# display_zm1000_rev_a.net
KiCad netlist of a schematic drawn in EAGLE
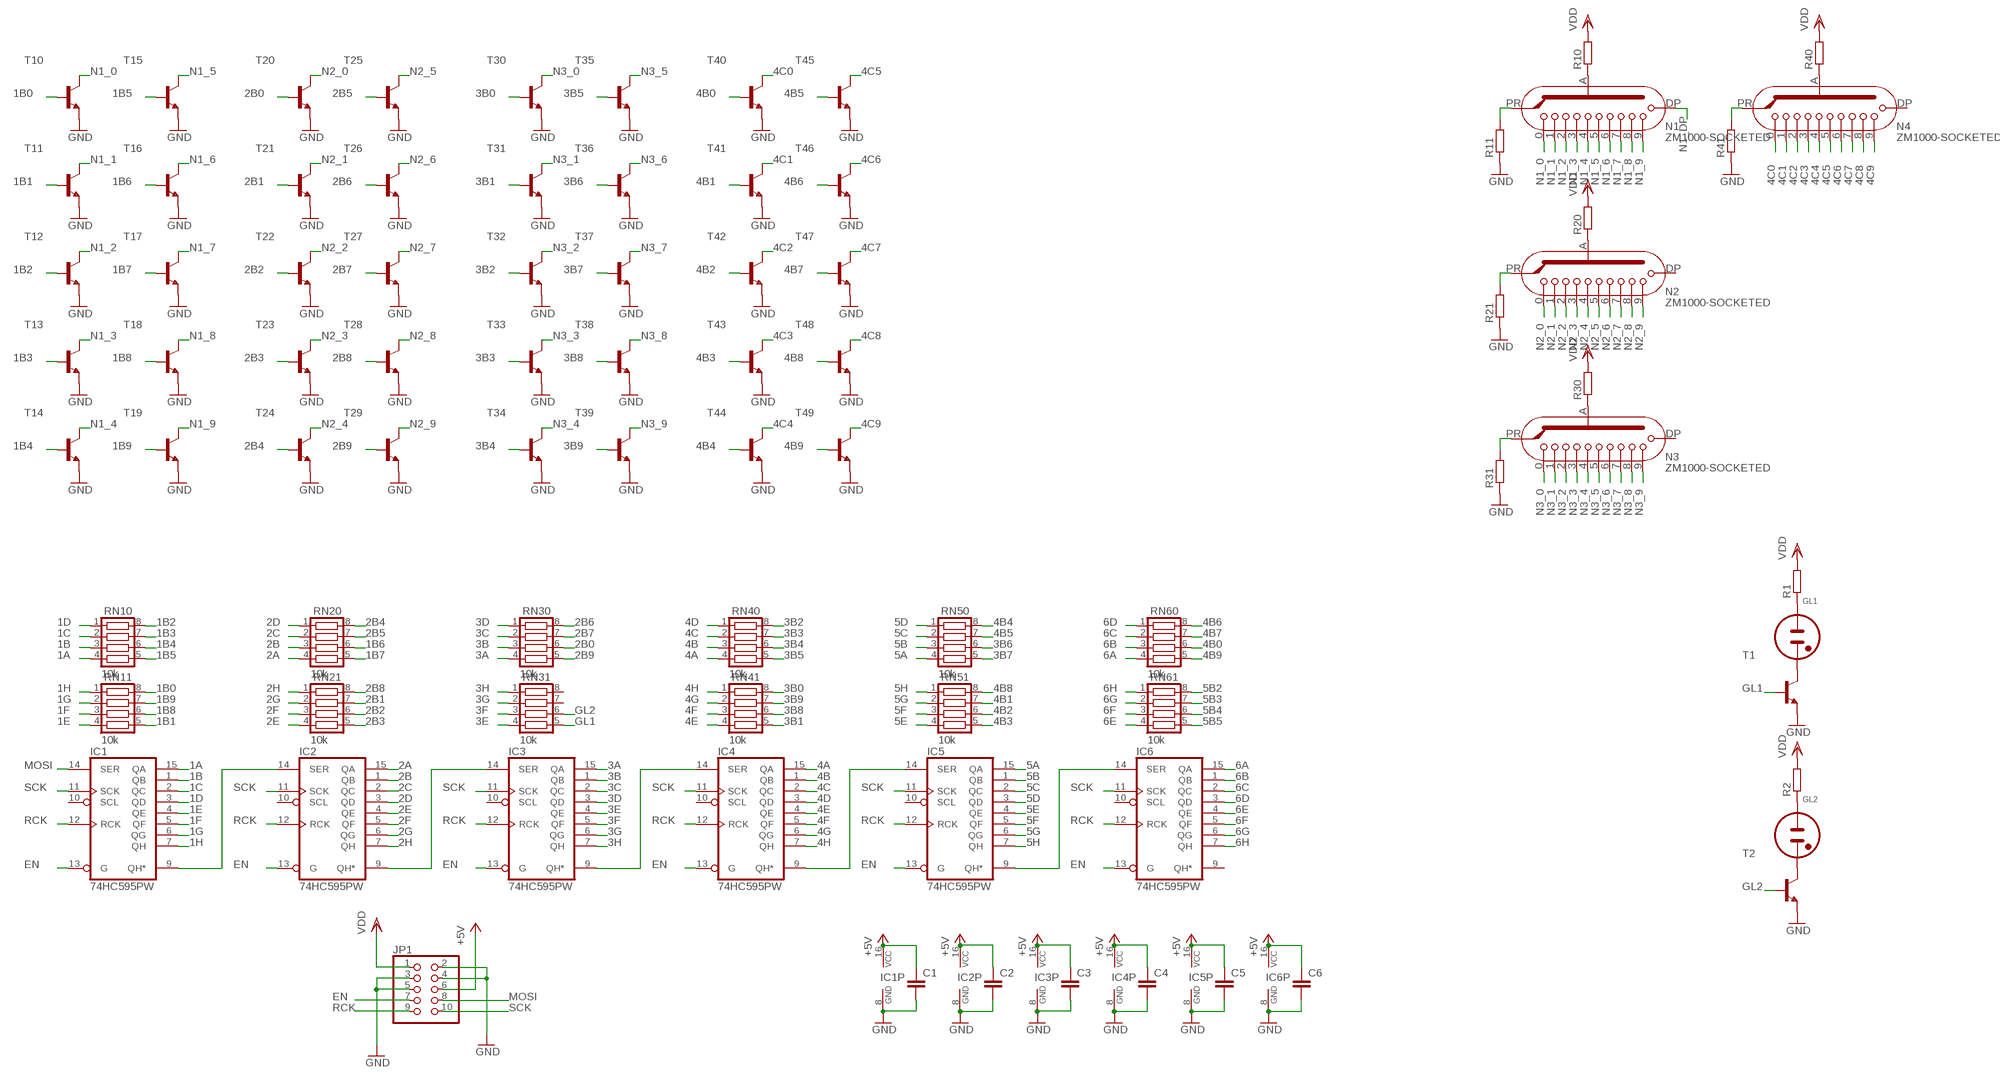
[diagram p0: schematic, sheet 1]

(export (version "E")
  (design (tool "Eeschema 10.0.6"))
  (components
    (comp (ref "C1")
      (value "C-EUC0603")
      (footprint "eagle-import:C0603")
      (libsource (lib "eagle-import") (part "C-EUC0603"))
    )
    (comp (ref "C2")
      (value "C-EUC0603")
      (footprint "eagle-import:C0603")
      (libsource (lib "eagle-import") (part "C-EUC0603"))
    )
    (comp (ref "C3")
      (value "C-EUC0603")
      (footprint "eagle-import:C0603")
      (libsource (lib "eagle-import") (part "C-EUC0603"))
    )
    (comp (ref "C4")
      (value "C-EUC0603")
      (footprint "eagle-import:C0603")
      (libsource (lib "eagle-import") (part "C-EUC0603"))
    )
    (comp (ref "C5")
      (value "C-EUC0603")
      (footprint "eagle-import:C0603")
      (libsource (lib "eagle-import") (part "C-EUC0603"))
    )
    (comp (ref "C6")
      (value "C-EUC0603")
      (footprint "eagle-import:C0603")
      (libsource (lib "eagle-import") (part "C-EUC0603"))
    )
    (comp (ref "GL1")
      (value "NE2-NEON-BULB-DRILL")
      (footprint "eagle-import:NE2-NEON-BULB-DRILL")
      (libsource (lib "eagle-import") (part "NE2-NEON-BULB-DRILL"))
    )
    (comp (ref "GL2")
      (value "NE2-NEON-BULB-DRILL")
      (footprint "eagle-import:NE2-NEON-BULB-DRILL")
      (libsource (lib "eagle-import") (part "NE2-NEON-BULB-DRILL"))
    )
    (comp (ref "IC1")
      (value "74HC595PW")
      (footprint "eagle-import:TSSOP16")
      (libsource (lib "eagle-import") (part "74595PWHC"))
    )
    (comp (ref "IC2")
      (value "74HC595PW")
      (footprint "eagle-import:TSSOP16")
      (libsource (lib "eagle-import") (part "74595PWHC"))
    )
    (comp (ref "IC3")
      (value "74HC595PW")
      (footprint "eagle-import:TSSOP16")
      (libsource (lib "eagle-import") (part "74595PWHC"))
    )
    (comp (ref "IC4")
      (value "74HC595PW")
      (footprint "eagle-import:TSSOP16")
      (libsource (lib "eagle-import") (part "74595PWHC"))
    )
    (comp (ref "IC5")
      (value "74HC595PW")
      (footprint "eagle-import:TSSOP16")
      (libsource (lib "eagle-import") (part "74595PWHC"))
    )
    (comp (ref "IC6")
      (value "74HC595PW")
      (footprint "eagle-import:TSSOP16")
      (libsource (lib "eagle-import") (part "74595PWHC"))
    )
    (comp (ref "JP1")
      (value "PINHD-2X5_2.54-SMD")
      (footprint "eagle-import:2X05SMD")
      (libsource (lib "eagle-import") (part "PINHD-2X5_2.54-SMD"))
    )
    (comp (ref "N1")
      (value "ZM1000-SOCKETED")
      (footprint "eagle-import:ZM1000-SOCKETED")
      (libsource (lib "eagle-import") (part "ZM1000-SOCKETED"))
    )
    (comp (ref "N2")
      (value "ZM1000-SOCKETED")
      (footprint "eagle-import:ZM1000-SOCKETED")
      (libsource (lib "eagle-import") (part "ZM1000-SOCKETED"))
    )
    (comp (ref "N3")
      (value "ZM1000-SOCKETED")
      (footprint "eagle-import:ZM1000-SOCKETED")
      (libsource (lib "eagle-import") (part "ZM1000-SOCKETED"))
    )
    (comp (ref "N4")
      (value "ZM1000-SOCKETED")
      (footprint "eagle-import:ZM1000-SOCKETED")
      (libsource (lib "eagle-import") (part "ZM1000-SOCKETED"))
    )
    (comp (ref "R1")
      (value "R-EU_R0603")
      (footprint "eagle-import:R0603")
      (libsource (lib "eagle-import") (part "R-EU_R0603"))
    )
    (comp (ref "R2")
      (value "R-EU_R0603")
      (footprint "eagle-import:R0603")
      (libsource (lib "eagle-import") (part "R-EU_R0603"))
    )
    (comp (ref "R10")
      (value "R-EU_R0603")
      (footprint "eagle-import:R0603")
      (libsource (lib "eagle-import") (part "R-EU_R0603"))
    )
    (comp (ref "R11")
      (value "R-EU_R0603")
      (footprint "eagle-import:R0603")
      (libsource (lib "eagle-import") (part "R-EU_R0603"))
    )
    (comp (ref "R20")
      (value "R-EU_R0603")
      (footprint "eagle-import:R0603")
      (libsource (lib "eagle-import") (part "R-EU_R0603"))
    )
    (comp (ref "R21")
      (value "R-EU_R0603")
      (footprint "eagle-import:R0603")
      (libsource (lib "eagle-import") (part "R-EU_R0603"))
    )
    (comp (ref "R30")
      (value "R-EU_R0603")
      (footprint "eagle-import:R0603")
      (libsource (lib "eagle-import") (part "R-EU_R0603"))
    )
    (comp (ref "R31")
      (value "R-EU_R0603")
      (footprint "eagle-import:R0603")
      (libsource (lib "eagle-import") (part "R-EU_R0603"))
    )
    (comp (ref "R40")
      (value "R-EU_R0603")
      (footprint "eagle-import:R0603")
      (libsource (lib "eagle-import") (part "R-EU_R0603"))
    )
    (comp (ref "R41")
      (value "R-EU_R0603")
      (footprint "eagle-import:R0603")
      (libsource (lib "eagle-import") (part "R-EU_R0603"))
    )
    (comp (ref "RN10")
      (value "10k")
      (footprint "eagle-import:CTS742C083")
      (fields (field (name "OC_FARNELL") "unknown") (field (name "OC_NEWARK") "unknown"))
      (libsource (lib "eagle-import") (part "CTS742C083"))
    )
    (comp (ref "RN11")
      (value "10k")
      (footprint "eagle-import:CTS742C083")
      (fields (field (name "OC_FARNELL") "unknown") (field (name "OC_NEWARK") "unknown"))
      (libsource (lib "eagle-import") (part "CTS742C083"))
    )
    (comp (ref "RN20")
      (value "10k")
      (footprint "eagle-import:CTS742C083")
      (fields (field (name "OC_FARNELL") "unknown") (field (name "OC_NEWARK") "unknown"))
      (libsource (lib "eagle-import") (part "CTS742C083"))
    )
    (comp (ref "RN21")
      (value "10k")
      (footprint "eagle-import:CTS742C083")
      (fields (field (name "OC_FARNELL") "unknown") (field (name "OC_NEWARK") "unknown"))
      (libsource (lib "eagle-import") (part "CTS742C083"))
    )
    (comp (ref "RN30")
      (value "10k")
      (footprint "eagle-import:CTS742C083")
      (fields (field (name "OC_FARNELL") "unknown") (field (name "OC_NEWARK") "unknown"))
      (libsource (lib "eagle-import") (part "CTS742C083"))
    )
    (comp (ref "RN31")
      (value "10k")
      (footprint "eagle-import:CTS742C083")
      (fields (field (name "OC_FARNELL") "unknown") (field (name "OC_NEWARK") "unknown"))
      (libsource (lib "eagle-import") (part "CTS742C083"))
    )
    (comp (ref "RN40")
      (value "10k")
      (footprint "eagle-import:CTS742C083")
      (fields (field (name "OC_FARNELL") "unknown") (field (name "OC_NEWARK") "unknown"))
      (libsource (lib "eagle-import") (part "CTS742C083"))
    )
    (comp (ref "RN41")
      (value "10k")
      (footprint "eagle-import:CTS742C083")
      (fields (field (name "OC_FARNELL") "unknown") (field (name "OC_NEWARK") "unknown"))
      (libsource (lib "eagle-import") (part "CTS742C083"))
    )
    (comp (ref "RN50")
      (value "10k")
      (footprint "eagle-import:CTS742C083")
      (fields (field (name "OC_FARNELL") "unknown") (field (name "OC_NEWARK") "unknown"))
      (libsource (lib "eagle-import") (part "CTS742C083"))
    )
    (comp (ref "RN51")
      (value "10k")
      (footprint "eagle-import:CTS742C083")
      (fields (field (name "OC_FARNELL") "unknown") (field (name "OC_NEWARK") "unknown"))
      (libsource (lib "eagle-import") (part "CTS742C083"))
    )
    (comp (ref "RN60")
      (value "10k")
      (footprint "eagle-import:CTS742C083")
      (fields (field (name "OC_FARNELL") "unknown") (field (name "OC_NEWARK") "unknown"))
      (libsource (lib "eagle-import") (part "CTS742C083"))
    )
    (comp (ref "RN61")
      (value "10k")
      (footprint "eagle-import:CTS742C083")
      (fields (field (name "OC_FARNELL") "unknown") (field (name "OC_NEWARK") "unknown"))
      (libsource (lib "eagle-import") (part "CTS742C083"))
    )
    (comp (ref "T1")
      (value "SMBTA42")
      (footprint "eagle-import:SOT23")
      (libsource (lib "eagle-import") (part "SMBTA42"))
    )
    (comp (ref "T2")
      (value "SMBTA42")
      (footprint "eagle-import:SOT23")
      (libsource (lib "eagle-import") (part "SMBTA42"))
    )
    (comp (ref "T10")
      (value "SMBTA42")
      (footprint "eagle-import:SOT23")
      (libsource (lib "eagle-import") (part "SMBTA42"))
    )
    (comp (ref "T11")
      (value "SMBTA42")
      (footprint "eagle-import:SOT23")
      (libsource (lib "eagle-import") (part "SMBTA42"))
    )
    (comp (ref "T12")
      (value "SMBTA42")
      (footprint "eagle-import:SOT23")
      (libsource (lib "eagle-import") (part "SMBTA42"))
    )
    (comp (ref "T13")
      (value "SMBTA42")
      (footprint "eagle-import:SOT23")
      (libsource (lib "eagle-import") (part "SMBTA42"))
    )
    (comp (ref "T14")
      (value "SMBTA42")
      (footprint "eagle-import:SOT23")
      (libsource (lib "eagle-import") (part "SMBTA42"))
    )
    (comp (ref "T15")
      (value "SMBTA42")
      (footprint "eagle-import:SOT23")
      (libsource (lib "eagle-import") (part "SMBTA42"))
    )
    (comp (ref "T16")
      (value "SMBTA42")
      (footprint "eagle-import:SOT23")
      (libsource (lib "eagle-import") (part "SMBTA42"))
    )
    (comp (ref "T17")
      (value "SMBTA42")
      (footprint "eagle-import:SOT23")
      (libsource (lib "eagle-import") (part "SMBTA42"))
    )
    (comp (ref "T18")
      (value "SMBTA42")
      (footprint "eagle-import:SOT23")
      (libsource (lib "eagle-import") (part "SMBTA42"))
    )
    (comp (ref "T19")
      (value "SMBTA42")
      (footprint "eagle-import:SOT23")
      (libsource (lib "eagle-import") (part "SMBTA42"))
    )
    (comp (ref "T20")
      (value "SMBTA42")
      (footprint "eagle-import:SOT23")
      (libsource (lib "eagle-import") (part "SMBTA42"))
    )
    (comp (ref "T21")
      (value "SMBTA42")
      (footprint "eagle-import:SOT23")
      (libsource (lib "eagle-import") (part "SMBTA42"))
    )
    (comp (ref "T22")
      (value "SMBTA42")
      (footprint "eagle-import:SOT23")
      (libsource (lib "eagle-import") (part "SMBTA42"))
    )
    (comp (ref "T23")
      (value "SMBTA42")
      (footprint "eagle-import:SOT23")
      (libsource (lib "eagle-import") (part "SMBTA42"))
    )
    (comp (ref "T24")
      (value "SMBTA42")
      (footprint "eagle-import:SOT23")
      (libsource (lib "eagle-import") (part "SMBTA42"))
    )
    (comp (ref "T25")
      (value "SMBTA42")
      (footprint "eagle-import:SOT23")
      (libsource (lib "eagle-import") (part "SMBTA42"))
    )
    (comp (ref "T26")
      (value "SMBTA42")
      (footprint "eagle-import:SOT23")
      (libsource (lib "eagle-import") (part "SMBTA42"))
    )
    (comp (ref "T27")
      (value "SMBTA42")
      (footprint "eagle-import:SOT23")
      (libsource (lib "eagle-import") (part "SMBTA42"))
    )
    (comp (ref "T28")
      (value "SMBTA42")
      (footprint "eagle-import:SOT23")
      (libsource (lib "eagle-import") (part "SMBTA42"))
    )
    (comp (ref "T29")
      (value "SMBTA42")
      (footprint "eagle-import:SOT23")
      (libsource (lib "eagle-import") (part "SMBTA42"))
    )
    (comp (ref "T30")
      (value "SMBTA42")
      (footprint "eagle-import:SOT23")
      (libsource (lib "eagle-import") (part "SMBTA42"))
    )
    (comp (ref "T31")
      (value "SMBTA42")
      (footprint "eagle-import:SOT23")
      (libsource (lib "eagle-import") (part "SMBTA42"))
    )
    (comp (ref "T32")
      (value "SMBTA42")
      (footprint "eagle-import:SOT23")
      (libsource (lib "eagle-import") (part "SMBTA42"))
    )
    (comp (ref "T33")
      (value "SMBTA42")
      (footprint "eagle-import:SOT23")
      (libsource (lib "eagle-import") (part "SMBTA42"))
    )
    (comp (ref "T34")
      (value "SMBTA42")
      (footprint "eagle-import:SOT23")
      (libsource (lib "eagle-import") (part "SMBTA42"))
    )
    (comp (ref "T35")
      (value "SMBTA42")
      (footprint "eagle-import:SOT23")
      (libsource (lib "eagle-import") (part "SMBTA42"))
    )
    (comp (ref "T36")
      (value "SMBTA42")
      (footprint "eagle-import:SOT23")
      (libsource (lib "eagle-import") (part "SMBTA42"))
    )
    (comp (ref "T37")
      (value "SMBTA42")
      (footprint "eagle-import:SOT23")
      (libsource (lib "eagle-import") (part "SMBTA42"))
    )
    (comp (ref "T38")
      (value "SMBTA42")
      (footprint "eagle-import:SOT23")
      (libsource (lib "eagle-import") (part "SMBTA42"))
    )
    (comp (ref "T39")
      (value "SMBTA42")
      (footprint "eagle-import:SOT23")
      (libsource (lib "eagle-import") (part "SMBTA42"))
    )
    (comp (ref "T40")
      (value "SMBTA42")
      (footprint "eagle-import:SOT23")
      (libsource (lib "eagle-import") (part "SMBTA42"))
    )
    (comp (ref "T41")
      (value "SMBTA42")
      (footprint "eagle-import:SOT23")
      (libsource (lib "eagle-import") (part "SMBTA42"))
    )
    (comp (ref "T42")
      (value "SMBTA42")
      (footprint "eagle-import:SOT23")
      (libsource (lib "eagle-import") (part "SMBTA42"))
    )
    (comp (ref "T43")
      (value "SMBTA42")
      (footprint "eagle-import:SOT23")
      (libsource (lib "eagle-import") (part "SMBTA42"))
    )
    (comp (ref "T44")
      (value "SMBTA42")
      (footprint "eagle-import:SOT23")
      (libsource (lib "eagle-import") (part "SMBTA42"))
    )
    (comp (ref "T45")
      (value "SMBTA42")
      (footprint "eagle-import:SOT23")
      (libsource (lib "eagle-import") (part "SMBTA42"))
    )
    (comp (ref "T46")
      (value "SMBTA42")
      (footprint "eagle-import:SOT23")
      (libsource (lib "eagle-import") (part "SMBTA42"))
    )
    (comp (ref "T47")
      (value "SMBTA42")
      (footprint "eagle-import:SOT23")
      (libsource (lib "eagle-import") (part "SMBTA42"))
    )
    (comp (ref "T48")
      (value "SMBTA42")
      (footprint "eagle-import:SOT23")
      (libsource (lib "eagle-import") (part "SMBTA42"))
    )
    (comp (ref "T49")
      (value "SMBTA42")
      (footprint "eagle-import:SOT23")
      (libsource (lib "eagle-import") (part "SMBTA42"))
    )
  )
  (nets
    (net (code "1") (name "+5V") (class "Default")
      (node (ref "C1") (pin "1") (pinfunction "1_1") (pintype "passive"))
      (node (ref "C2") (pin "1") (pinfunction "1_1") (pintype "passive"))
      (node (ref "C3") (pin "1") (pinfunction "1_1") (pintype "passive"))
      (node (ref "C4") (pin "1") (pinfunction "1_1") (pintype "passive"))
      (node (ref "C5") (pin "1") (pinfunction "1_1") (pintype "passive"))
      (node (ref "C6") (pin "1") (pinfunction "1_1") (pintype "passive"))
      (node (ref "IC1") (pin "16") (pinfunction "VCC_16") (pintype "power_in"))
      (node (ref "IC2") (pin "16") (pinfunction "VCC_16") (pintype "power_in"))
      (node (ref "IC3") (pin "16") (pinfunction "VCC_16") (pintype "power_in"))
      (node (ref "IC4") (pin "16") (pinfunction "VCC_16") (pintype "power_in"))
      (node (ref "IC5") (pin "16") (pinfunction "VCC_16") (pintype "power_in"))
      (node (ref "IC6") (pin "16") (pinfunction "VCC_16") (pintype "power_in"))
      (node (ref "JP1") (pin "6") (pinfunction "6_6") (pintype "passive"))
    )
    (net (code "2") (name "/1A") (class "Default")
      (node (ref "IC1") (pin "15") (pinfunction "QA_15") (pintype "tri_state"))
      (node (ref "RN10") (pin "4") (pinfunction "4_4") (pintype "passive"))
    )
    (net (code "3") (name "/1B") (class "Default")
      (node (ref "IC1") (pin "1") (pinfunction "QB_1") (pintype "tri_state"))
      (node (ref "RN10") (pin "3") (pinfunction "3_3") (pintype "passive"))
    )
    (net (code "4") (name "/1B0") (class "Default")
      (node (ref "RN11") (pin "8") (pinfunction "8_8") (pintype "passive"))
      (node (ref "T10") (pin "1") (pinfunction "B_1") (pintype "passive"))
    )
    (net (code "5") (name "/1B1") (class "Default")
      (node (ref "RN11") (pin "5") (pinfunction "5_5") (pintype "passive"))
      (node (ref "T11") (pin "1") (pinfunction "B_1") (pintype "passive"))
    )
    (net (code "6") (name "/1B2") (class "Default")
      (node (ref "RN10") (pin "8") (pinfunction "8_8") (pintype "passive"))
      (node (ref "T12") (pin "1") (pinfunction "B_1") (pintype "passive"))
    )
    (net (code "7") (name "/1B3") (class "Default")
      (node (ref "RN10") (pin "7") (pinfunction "7_7") (pintype "passive"))
      (node (ref "T13") (pin "1") (pinfunction "B_1") (pintype "passive"))
    )
    (net (code "8") (name "/1B4") (class "Default")
      (node (ref "RN10") (pin "6") (pinfunction "6_6") (pintype "passive"))
      (node (ref "T14") (pin "1") (pinfunction "B_1") (pintype "passive"))
    )
    (net (code "9") (name "/1B5") (class "Default")
      (node (ref "RN10") (pin "5") (pinfunction "5_5") (pintype "passive"))
      (node (ref "T15") (pin "1") (pinfunction "B_1") (pintype "passive"))
    )
    (net (code "10") (name "/1B6") (class "Default")
      (node (ref "RN20") (pin "6") (pinfunction "6_6") (pintype "passive"))
      (node (ref "T16") (pin "1") (pinfunction "B_1") (pintype "passive"))
    )
    (net (code "11") (name "/1B7") (class "Default")
      (node (ref "RN20") (pin "5") (pinfunction "5_5") (pintype "passive"))
      (node (ref "T17") (pin "1") (pinfunction "B_1") (pintype "passive"))
    )
    (net (code "12") (name "/1B8") (class "Default")
      (node (ref "RN11") (pin "6") (pinfunction "6_6") (pintype "passive"))
      (node (ref "T18") (pin "1") (pinfunction "B_1") (pintype "passive"))
    )
    (net (code "13") (name "/1B9") (class "Default")
      (node (ref "RN11") (pin "7") (pinfunction "7_7") (pintype "passive"))
      (node (ref "T19") (pin "1") (pinfunction "B_1") (pintype "passive"))
    )
    (net (code "14") (name "/1C") (class "Default")
      (node (ref "IC1") (pin "2") (pinfunction "QC_2") (pintype "tri_state"))
      (node (ref "RN10") (pin "2") (pinfunction "2_2") (pintype "passive"))
    )
    (net (code "15") (name "/1D") (class "Default")
      (node (ref "IC1") (pin "3") (pinfunction "QD_3") (pintype "tri_state"))
      (node (ref "RN10") (pin "1") (pinfunction "1_1") (pintype "passive"))
    )
    (net (code "16") (name "/1E") (class "Default")
      (node (ref "IC1") (pin "4") (pinfunction "QE_4") (pintype "tri_state"))
      (node (ref "RN11") (pin "4") (pinfunction "4_4") (pintype "passive"))
    )
    (net (code "17") (name "/1F") (class "Default")
      (node (ref "IC1") (pin "5") (pinfunction "QF_5") (pintype "tri_state"))
      (node (ref "RN11") (pin "3") (pinfunction "3_3") (pintype "passive"))
    )
    (net (code "18") (name "/1G") (class "Default")
      (node (ref "IC1") (pin "6") (pinfunction "QG_6") (pintype "tri_state"))
      (node (ref "RN11") (pin "2") (pinfunction "2_2") (pintype "passive"))
    )
    (net (code "19") (name "/1H") (class "Default")
      (node (ref "IC1") (pin "7") (pinfunction "QH_7") (pintype "tri_state"))
      (node (ref "RN11") (pin "1") (pinfunction "1_1") (pintype "passive"))
    )
    (net (code "20") (name "/2A") (class "Default")
      (node (ref "IC2") (pin "15") (pinfunction "QA_15") (pintype "tri_state"))
      (node (ref "RN20") (pin "4") (pinfunction "4_4") (pintype "passive"))
    )
    (net (code "21") (name "/2B") (class "Default")
      (node (ref "IC2") (pin "1") (pinfunction "QB_1") (pintype "tri_state"))
      (node (ref "RN20") (pin "3") (pinfunction "3_3") (pintype "passive"))
    )
    (net (code "22") (name "/2B0") (class "Default")
      (node (ref "RN30") (pin "6") (pinfunction "6_6") (pintype "passive"))
      (node (ref "T20") (pin "1") (pinfunction "B_1") (pintype "passive"))
    )
    (net (code "23") (name "/2B1") (class "Default")
      (node (ref "RN21") (pin "7") (pinfunction "7_7") (pintype "passive"))
      (node (ref "T21") (pin "1") (pinfunction "B_1") (pintype "passive"))
    )
    (net (code "24") (name "/2B2") (class "Default")
      (node (ref "RN21") (pin "6") (pinfunction "6_6") (pintype "passive"))
      (node (ref "T22") (pin "1") (pinfunction "B_1") (pintype "passive"))
    )
    (net (code "25") (name "/2B3") (class "Default")
      (node (ref "RN21") (pin "5") (pinfunction "5_5") (pintype "passive"))
      (node (ref "T23") (pin "1") (pinfunction "B_1") (pintype "passive"))
    )
    (net (code "26") (name "/2B4") (class "Default")
      (node (ref "RN20") (pin "8") (pinfunction "8_8") (pintype "passive"))
      (node (ref "T24") (pin "1") (pinfunction "B_1") (pintype "passive"))
    )
    (net (code "27") (name "/2B5") (class "Default")
      (node (ref "RN20") (pin "7") (pinfunction "7_7") (pintype "passive"))
      (node (ref "T25") (pin "1") (pinfunction "B_1") (pintype "passive"))
    )
    (net (code "28") (name "/2B6") (class "Default")
      (node (ref "RN30") (pin "8") (pinfunction "8_8") (pintype "passive"))
      (node (ref "T26") (pin "1") (pinfunction "B_1") (pintype "passive"))
    )
    (net (code "29") (name "/2B7") (class "Default")
      (node (ref "RN30") (pin "7") (pinfunction "7_7") (pintype "passive"))
      (node (ref "T27") (pin "1") (pinfunction "B_1") (pintype "passive"))
    )
    (net (code "30") (name "/2B8") (class "Default")
      (node (ref "RN21") (pin "8") (pinfunction "8_8") (pintype "passive"))
      (node (ref "T28") (pin "1") (pinfunction "B_1") (pintype "passive"))
    )
    (net (code "31") (name "/2B9") (class "Default")
      (node (ref "RN30") (pin "5") (pinfunction "5_5") (pintype "passive"))
      (node (ref "T29") (pin "1") (pinfunction "B_1") (pintype "passive"))
    )
    (net (code "32") (name "/2C") (class "Default")
      (node (ref "IC2") (pin "2") (pinfunction "QC_2") (pintype "tri_state"))
      (node (ref "RN20") (pin "2") (pinfunction "2_2") (pintype "passive"))
    )
    (net (code "33") (name "/2D") (class "Default")
      (node (ref "IC2") (pin "3") (pinfunction "QD_3") (pintype "tri_state"))
      (node (ref "RN20") (pin "1") (pinfunction "1_1") (pintype "passive"))
    )
    (net (code "34") (name "/2E") (class "Default")
      (node (ref "IC2") (pin "4") (pinfunction "QE_4") (pintype "tri_state"))
      (node (ref "RN21") (pin "4") (pinfunction "4_4") (pintype "passive"))
    )
    (net (code "35") (name "/2F") (class "Default")
      (node (ref "IC2") (pin "5") (pinfunction "QF_5") (pintype "tri_state"))
      (node (ref "RN21") (pin "3") (pinfunction "3_3") (pintype "passive"))
    )
    (net (code "36") (name "/2G") (class "Default")
      (node (ref "IC2") (pin "6") (pinfunction "QG_6") (pintype "tri_state"))
      (node (ref "RN21") (pin "2") (pinfunction "2_2") (pintype "passive"))
    )
    (net (code "37") (name "/2H") (class "Default")
      (node (ref "IC2") (pin "7") (pinfunction "QH_7") (pintype "tri_state"))
      (node (ref "RN21") (pin "1") (pinfunction "1_1") (pintype "passive"))
    )
    (net (code "38") (name "/3A") (class "Default")
      (node (ref "IC3") (pin "15") (pinfunction "QA_15") (pintype "tri_state"))
      (node (ref "RN30") (pin "4") (pinfunction "4_4") (pintype "passive"))
    )
    (net (code "39") (name "/3B") (class "Default")
      (node (ref "IC3") (pin "1") (pinfunction "QB_1") (pintype "tri_state"))
      (node (ref "RN30") (pin "3") (pinfunction "3_3") (pintype "passive"))
    )
    (net (code "40") (name "/3B0") (class "Default")
      (node (ref "RN41") (pin "8") (pinfunction "8_8") (pintype "passive"))
      (node (ref "T30") (pin "1") (pinfunction "B_1") (pintype "passive"))
    )
    (net (code "41") (name "/3B1") (class "Default")
      (node (ref "RN41") (pin "5") (pinfunction "5_5") (pintype "passive"))
      (node (ref "T31") (pin "1") (pinfunction "B_1") (pintype "passive"))
    )
    (net (code "42") (name "/3B2") (class "Default")
      (node (ref "RN40") (pin "8") (pinfunction "8_8") (pintype "passive"))
      (node (ref "T32") (pin "1") (pinfunction "B_1") (pintype "passive"))
    )
    (net (code "43") (name "/3B3") (class "Default")
      (node (ref "RN40") (pin "7") (pinfunction "7_7") (pintype "passive"))
      (node (ref "T33") (pin "1") (pinfunction "B_1") (pintype "passive"))
    )
    (net (code "44") (name "/3B4") (class "Default")
      (node (ref "RN40") (pin "6") (pinfunction "6_6") (pintype "passive"))
      (node (ref "T34") (pin "1") (pinfunction "B_1") (pintype "passive"))
    )
    (net (code "45") (name "/3B5") (class "Default")
      (node (ref "RN40") (pin "5") (pinfunction "5_5") (pintype "passive"))
      (node (ref "T35") (pin "1") (pinfunction "B_1") (pintype "passive"))
    )
    (net (code "46") (name "/3B6") (class "Default")
      (node (ref "RN50") (pin "6") (pinfunction "6_6") (pintype "passive"))
      (node (ref "T36") (pin "1") (pinfunction "B_1") (pintype "passive"))
    )
    (net (code "47") (name "/3B7") (class "Default")
      (node (ref "RN50") (pin "5") (pinfunction "5_5") (pintype "passive"))
      (node (ref "T37") (pin "1") (pinfunction "B_1") (pintype "passive"))
    )
    (net (code "48") (name "/3B8") (class "Default")
      (node (ref "RN41") (pin "6") (pinfunction "6_6") (pintype "passive"))
      (node (ref "T38") (pin "1") (pinfunction "B_1") (pintype "passive"))
    )
    (net (code "49") (name "/3B9") (class "Default")
      (node (ref "RN41") (pin "7") (pinfunction "7_7") (pintype "passive"))
      (node (ref "T39") (pin "1") (pinfunction "B_1") (pintype "passive"))
    )
    (net (code "50") (name "/3C") (class "Default")
      (node (ref "IC3") (pin "2") (pinfunction "QC_2") (pintype "tri_state"))
      (node (ref "RN30") (pin "2") (pinfunction "2_2") (pintype "passive"))
    )
    (net (code "51") (name "/3D") (class "Default")
      (node (ref "IC3") (pin "3") (pinfunction "QD_3") (pintype "tri_state"))
      (node (ref "RN30") (pin "1") (pinfunction "1_1") (pintype "passive"))
    )
    (net (code "52") (name "/3E") (class "Default")
      (node (ref "IC3") (pin "4") (pinfunction "QE_4") (pintype "tri_state"))
      (node (ref "RN31") (pin "4") (pinfunction "4_4") (pintype "passive"))
    )
    (net (code "53") (name "/3F") (class "Default")
      (node (ref "IC3") (pin "5") (pinfunction "QF_5") (pintype "tri_state"))
      (node (ref "RN31") (pin "3") (pinfunction "3_3") (pintype "passive"))
    )
    (net (code "54") (name "/3G") (class "Default")
      (node (ref "IC3") (pin "6") (pinfunction "QG_6") (pintype "tri_state"))
      (node (ref "RN31") (pin "2") (pinfunction "2_2") (pintype "passive"))
    )
    (net (code "55") (name "/3H") (class "Default")
      (node (ref "IC3") (pin "7") (pinfunction "QH_7") (pintype "tri_state"))
      (node (ref "RN31") (pin "1") (pinfunction "1_1") (pintype "passive"))
    )
    (net (code "56") (name "/4A") (class "Default")
      (node (ref "IC4") (pin "15") (pinfunction "QA_15") (pintype "tri_state"))
      (node (ref "RN40") (pin "4") (pinfunction "4_4") (pintype "passive"))
    )
    (net (code "57") (name "/4B") (class "Default")
      (node (ref "IC4") (pin "1") (pinfunction "QB_1") (pintype "tri_state"))
      (node (ref "RN40") (pin "3") (pinfunction "3_3") (pintype "passive"))
    )
    (net (code "58") (name "/4B0") (class "Default")
      (node (ref "RN60") (pin "6") (pinfunction "6_6") (pintype "passive"))
      (node (ref "T40") (pin "1") (pinfunction "B_1") (pintype "passive"))
    )
    (net (code "59") (name "/4B1") (class "Default")
      (node (ref "RN51") (pin "7") (pinfunction "7_7") (pintype "passive"))
      (node (ref "T41") (pin "1") (pinfunction "B_1") (pintype "passive"))
    )
    (net (code "60") (name "/4B2") (class "Default")
      (node (ref "RN51") (pin "6") (pinfunction "6_6") (pintype "passive"))
      (node (ref "T42") (pin "1") (pinfunction "B_1") (pintype "passive"))
    )
    (net (code "61") (name "/4B3") (class "Default")
      (node (ref "RN51") (pin "5") (pinfunction "5_5") (pintype "passive"))
      (node (ref "T43") (pin "1") (pinfunction "B_1") (pintype "passive"))
    )
    (net (code "62") (name "/4B4") (class "Default")
      (node (ref "RN50") (pin "8") (pinfunction "8_8") (pintype "passive"))
      (node (ref "T44") (pin "1") (pinfunction "B_1") (pintype "passive"))
    )
    (net (code "63") (name "/4B5") (class "Default")
      (node (ref "RN50") (pin "7") (pinfunction "7_7") (pintype "passive"))
      (node (ref "T45") (pin "1") (pinfunction "B_1") (pintype "passive"))
    )
    (net (code "64") (name "/4B6") (class "Default")
      (node (ref "RN60") (pin "8") (pinfunction "8_8") (pintype "passive"))
      (node (ref "T46") (pin "1") (pinfunction "B_1") (pintype "passive"))
    )
    (net (code "65") (name "/4B7") (class "Default")
      (node (ref "RN60") (pin "7") (pinfunction "7_7") (pintype "passive"))
      (node (ref "T47") (pin "1") (pinfunction "B_1") (pintype "passive"))
    )
    (net (code "66") (name "/4B8") (class "Default")
      (node (ref "RN51") (pin "8") (pinfunction "8_8") (pintype "passive"))
      (node (ref "T48") (pin "1") (pinfunction "B_1") (pintype "passive"))
    )
    (net (code "67") (name "/4B9") (class "Default")
      (node (ref "RN60") (pin "5") (pinfunction "5_5") (pintype "passive"))
      (node (ref "T49") (pin "1") (pinfunction "B_1") (pintype "passive"))
    )
    (net (code "68") (name "/4C") (class "Default")
      (node (ref "IC4") (pin "2") (pinfunction "QC_2") (pintype "tri_state"))
      (node (ref "RN40") (pin "2") (pinfunction "2_2") (pintype "passive"))
    )
    (net (code "69") (name "/4C0") (class "Default")
      (node (ref "N4") (pin "K0") (pinfunction "0_K0") (pintype "bidirectional"))
      (node (ref "T40") (pin "3") (pinfunction "C_3") (pintype "passive"))
    )
    (net (code "70") (name "/4C1") (class "Default")
      (node (ref "N4") (pin "K1") (pinfunction "1_K1") (pintype "bidirectional"))
      (node (ref "T41") (pin "3") (pinfunction "C_3") (pintype "passive"))
    )
    (net (code "71") (name "/4C2") (class "Default")
      (node (ref "N4") (pin "K2") (pinfunction "2_K2") (pintype "bidirectional"))
      (node (ref "T42") (pin "3") (pinfunction "C_3") (pintype "passive"))
    )
    (net (code "72") (name "/4C3") (class "Default")
      (node (ref "N4") (pin "K3") (pinfunction "3_K3") (pintype "bidirectional"))
      (node (ref "T43") (pin "3") (pinfunction "C_3") (pintype "passive"))
    )
    (net (code "73") (name "/4C4") (class "Default")
      (node (ref "N4") (pin "K4") (pinfunction "4_K4") (pintype "bidirectional"))
      (node (ref "T44") (pin "3") (pinfunction "C_3") (pintype "passive"))
    )
    (net (code "74") (name "/4C5") (class "Default")
      (node (ref "N4") (pin "K5") (pinfunction "5_K5") (pintype "bidirectional"))
      (node (ref "T45") (pin "3") (pinfunction "C_3") (pintype "passive"))
    )
    (net (code "75") (name "/4C6") (class "Default")
      (node (ref "N4") (pin "K6") (pinfunction "6_K6") (pintype "bidirectional"))
      (node (ref "T46") (pin "3") (pinfunction "C_3") (pintype "passive"))
    )
    (net (code "76") (name "/4C7") (class "Default")
      (node (ref "N4") (pin "K7") (pinfunction "7_K7") (pintype "bidirectional"))
      (node (ref "T47") (pin "3") (pinfunction "C_3") (pintype "passive"))
    )
    (net (code "77") (name "/4C8") (class "Default")
      (node (ref "N4") (pin "K8") (pinfunction "8_K8") (pintype "bidirectional"))
      (node (ref "T48") (pin "3") (pinfunction "C_3") (pintype "passive"))
    )
    (net (code "78") (name "/4C9") (class "Default")
      (node (ref "N4") (pin "K9") (pinfunction "9_K9") (pintype "bidirectional"))
      (node (ref "T49") (pin "3") (pinfunction "C_3") (pintype "passive"))
    )
    (net (code "79") (name "/4D") (class "Default")
      (node (ref "IC4") (pin "3") (pinfunction "QD_3") (pintype "tri_state"))
      (node (ref "RN40") (pin "1") (pinfunction "1_1") (pintype "passive"))
    )
    (net (code "80") (name "/4E") (class "Default")
      (node (ref "IC4") (pin "4") (pinfunction "QE_4") (pintype "tri_state"))
      (node (ref "RN41") (pin "4") (pinfunction "4_4") (pintype "passive"))
    )
    (net (code "81") (name "/4F") (class "Default")
      (node (ref "IC4") (pin "5") (pinfunction "QF_5") (pintype "tri_state"))
      (node (ref "RN41") (pin "3") (pinfunction "3_3") (pintype "passive"))
    )
    (net (code "82") (name "/4G") (class "Default")
      (node (ref "IC4") (pin "6") (pinfunction "QG_6") (pintype "tri_state"))
      (node (ref "RN41") (pin "2") (pinfunction "2_2") (pintype "passive"))
    )
    (net (code "83") (name "/4H") (class "Default")
      (node (ref "IC4") (pin "7") (pinfunction "QH_7") (pintype "tri_state"))
      (node (ref "RN41") (pin "1") (pinfunction "1_1") (pintype "passive"))
    )
    (net (code "84") (name "/5A") (class "Default")
      (node (ref "IC5") (pin "15") (pinfunction "QA_15") (pintype "tri_state"))
      (node (ref "RN50") (pin "4") (pinfunction "4_4") (pintype "passive"))
    )
    (net (code "85") (name "/5B") (class "Default")
      (node (ref "IC5") (pin "1") (pinfunction "QB_1") (pintype "tri_state"))
      (node (ref "RN50") (pin "3") (pinfunction "3_3") (pintype "passive"))
    )
    (net (code "86") (name "/5B2") (class "Default")
      (node (ref "RN61") (pin "8") (pinfunction "8_8") (pintype "passive"))
    )
    (net (code "87") (name "/5B3") (class "Default")
      (node (ref "RN61") (pin "7") (pinfunction "7_7") (pintype "passive"))
    )
    (net (code "88") (name "/5B4") (class "Default")
      (node (ref "RN61") (pin "6") (pinfunction "6_6") (pintype "passive"))
    )
    (net (code "89") (name "/5B5") (class "Default")
      (node (ref "RN61") (pin "5") (pinfunction "5_5") (pintype "passive"))
    )
    (net (code "90") (name "/5C") (class "Default")
      (node (ref "IC5") (pin "2") (pinfunction "QC_2") (pintype "tri_state"))
      (node (ref "RN50") (pin "2") (pinfunction "2_2") (pintype "passive"))
    )
    (net (code "91") (name "/5D") (class "Default")
      (node (ref "IC5") (pin "3") (pinfunction "QD_3") (pintype "tri_state"))
      (node (ref "RN50") (pin "1") (pinfunction "1_1") (pintype "passive"))
    )
    (net (code "92") (name "/5E") (class "Default")
      (node (ref "IC5") (pin "4") (pinfunction "QE_4") (pintype "tri_state"))
      (node (ref "RN51") (pin "4") (pinfunction "4_4") (pintype "passive"))
    )
    (net (code "93") (name "/5F") (class "Default")
      (node (ref "IC5") (pin "5") (pinfunction "QF_5") (pintype "tri_state"))
      (node (ref "RN51") (pin "3") (pinfunction "3_3") (pintype "passive"))
    )
    (net (code "94") (name "/5G") (class "Default")
      (node (ref "IC5") (pin "6") (pinfunction "QG_6") (pintype "tri_state"))
      (node (ref "RN51") (pin "2") (pinfunction "2_2") (pintype "passive"))
    )
    (net (code "95") (name "/5H") (class "Default")
      (node (ref "IC5") (pin "7") (pinfunction "QH_7") (pintype "tri_state"))
      (node (ref "RN51") (pin "1") (pinfunction "1_1") (pintype "passive"))
    )
    (net (code "96") (name "/6A") (class "Default")
      (node (ref "IC6") (pin "15") (pinfunction "QA_15") (pintype "tri_state"))
      (node (ref "RN60") (pin "4") (pinfunction "4_4") (pintype "passive"))
    )
    (net (code "97") (name "/6B") (class "Default")
      (node (ref "IC6") (pin "1") (pinfunction "QB_1") (pintype "tri_state"))
      (node (ref "RN60") (pin "3") (pinfunction "3_3") (pintype "passive"))
    )
    (net (code "98") (name "/6C") (class "Default")
      (node (ref "IC6") (pin "2") (pinfunction "QC_2") (pintype "tri_state"))
      (node (ref "RN60") (pin "2") (pinfunction "2_2") (pintype "passive"))
    )
    (net (code "99") (name "/6D") (class "Default")
      (node (ref "IC6") (pin "3") (pinfunction "QD_3") (pintype "tri_state"))
      (node (ref "RN60") (pin "1") (pinfunction "1_1") (pintype "passive"))
    )
    (net (code "100") (name "/6E") (class "Default")
      (node (ref "IC6") (pin "4") (pinfunction "QE_4") (pintype "tri_state"))
      (node (ref "RN61") (pin "4") (pinfunction "4_4") (pintype "passive"))
    )
    (net (code "101") (name "/6F") (class "Default")
      (node (ref "IC6") (pin "5") (pinfunction "QF_5") (pintype "tri_state"))
      (node (ref "RN61") (pin "3") (pinfunction "3_3") (pintype "passive"))
    )
    (net (code "102") (name "/6G") (class "Default")
      (node (ref "IC6") (pin "6") (pinfunction "QG_6") (pintype "tri_state"))
      (node (ref "RN61") (pin "2") (pinfunction "2_2") (pintype "passive"))
    )
    (net (code "103") (name "/6H") (class "Default")
      (node (ref "IC6") (pin "7") (pinfunction "QH_7") (pintype "tri_state"))
      (node (ref "RN61") (pin "1") (pinfunction "1_1") (pintype "passive"))
    )
    (net (code "104") (name "/EN") (class "Default")
      (node (ref "IC1") (pin "13") (pinfunction "G_13") (pintype "input"))
      (node (ref "IC2") (pin "13") (pinfunction "G_13") (pintype "input"))
      (node (ref "IC3") (pin "13") (pinfunction "G_13") (pintype "input"))
      (node (ref "IC4") (pin "13") (pinfunction "G_13") (pintype "input"))
      (node (ref "IC5") (pin "13") (pinfunction "G_13") (pintype "input"))
      (node (ref "IC6") (pin "13") (pinfunction "G_13") (pintype "input"))
      (node (ref "JP1") (pin "7") (pinfunction "7_7") (pintype "passive"))
    )
    (net (code "105") (name "/GL1") (class "Default")
      (node (ref "RN31") (pin "5") (pinfunction "5_5") (pintype "passive"))
      (node (ref "T1") (pin "1") (pinfunction "B_1") (pintype "passive"))
    )
    (net (code "106") (name "/GL2") (class "Default")
      (node (ref "RN31") (pin "6") (pinfunction "6_6") (pintype "passive"))
      (node (ref "T2") (pin "1") (pinfunction "B_1") (pintype "passive"))
    )
    (net (code "107") (name "/MOSI") (class "Default")
      (node (ref "IC1") (pin "14") (pinfunction "SER_14") (pintype "input"))
      (node (ref "JP1") (pin "8") (pinfunction "8_8") (pintype "passive"))
    )
    (net (code "108") (name "/N1_0") (class "Default")
      (node (ref "N1") (pin "K0") (pinfunction "0_K0") (pintype "bidirectional"))
      (node (ref "T10") (pin "3") (pinfunction "C_3") (pintype "passive"))
    )
    (net (code "109") (name "/N1_1") (class "Default")
      (node (ref "N1") (pin "K1") (pinfunction "1_K1") (pintype "bidirectional"))
      (node (ref "T11") (pin "3") (pinfunction "C_3") (pintype "passive"))
    )
    (net (code "110") (name "/N1_2") (class "Default")
      (node (ref "N1") (pin "K2") (pinfunction "2_K2") (pintype "bidirectional"))
      (node (ref "T12") (pin "3") (pinfunction "C_3") (pintype "passive"))
    )
    (net (code "111") (name "/N1_3") (class "Default")
      (node (ref "N1") (pin "K3") (pinfunction "3_K3") (pintype "bidirectional"))
      (node (ref "T13") (pin "3") (pinfunction "C_3") (pintype "passive"))
    )
    (net (code "112") (name "/N1_4") (class "Default")
      (node (ref "N1") (pin "K4") (pinfunction "4_K4") (pintype "bidirectional"))
      (node (ref "T14") (pin "3") (pinfunction "C_3") (pintype "passive"))
    )
    (net (code "113") (name "/N1_5") (class "Default")
      (node (ref "N1") (pin "K5") (pinfunction "5_K5") (pintype "bidirectional"))
      (node (ref "T15") (pin "3") (pinfunction "C_3") (pintype "passive"))
    )
    (net (code "114") (name "/N1_6") (class "Default")
      (node (ref "N1") (pin "K6") (pinfunction "6_K6") (pintype "bidirectional"))
      (node (ref "T16") (pin "3") (pinfunction "C_3") (pintype "passive"))
    )
    (net (code "115") (name "/N1_7") (class "Default")
      (node (ref "N1") (pin "K7") (pinfunction "7_K7") (pintype "bidirectional"))
      (node (ref "T17") (pin "3") (pinfunction "C_3") (pintype "passive"))
    )
    (net (code "116") (name "/N1_8") (class "Default")
      (node (ref "N1") (pin "K8") (pinfunction "8_K8") (pintype "bidirectional"))
      (node (ref "T18") (pin "3") (pinfunction "C_3") (pintype "passive"))
    )
    (net (code "117") (name "/N1_9") (class "Default")
      (node (ref "N1") (pin "K9") (pinfunction "9_K9") (pintype "bidirectional"))
      (node (ref "T19") (pin "3") (pinfunction "C_3") (pintype "passive"))
    )
    (net (code "118") (name "/N1_DP") (class "Default")
      (node (ref "N1") (pin "KDP") (pinfunction "DP_KDP") (pintype "bidirectional"))
    )
    (net (code "119") (name "/N2_0") (class "Default")
      (node (ref "N2") (pin "K0") (pinfunction "0_K0") (pintype "bidirectional"))
      (node (ref "T20") (pin "3") (pinfunction "C_3") (pintype "passive"))
    )
    (net (code "120") (name "/N2_1") (class "Default")
      (node (ref "N2") (pin "K1") (pinfunction "1_K1") (pintype "bidirectional"))
      (node (ref "T21") (pin "3") (pinfunction "C_3") (pintype "passive"))
    )
    (net (code "121") (name "/N2_2") (class "Default")
      (node (ref "N2") (pin "K2") (pinfunction "2_K2") (pintype "bidirectional"))
      (node (ref "T22") (pin "3") (pinfunction "C_3") (pintype "passive"))
    )
    (net (code "122") (name "/N2_3") (class "Default")
      (node (ref "N2") (pin "K3") (pinfunction "3_K3") (pintype "bidirectional"))
      (node (ref "T23") (pin "3") (pinfunction "C_3") (pintype "passive"))
    )
    (net (code "123") (name "/N2_4") (class "Default")
      (node (ref "N2") (pin "K4") (pinfunction "4_K4") (pintype "bidirectional"))
      (node (ref "T24") (pin "3") (pinfunction "C_3") (pintype "passive"))
    )
    (net (code "124") (name "/N2_5") (class "Default")
      (node (ref "N2") (pin "K5") (pinfunction "5_K5") (pintype "bidirectional"))
      (node (ref "T25") (pin "3") (pinfunction "C_3") (pintype "passive"))
    )
    (net (code "125") (name "/N2_6") (class "Default")
      (node (ref "N2") (pin "K6") (pinfunction "6_K6") (pintype "bidirectional"))
      (node (ref "T26") (pin "3") (pinfunction "C_3") (pintype "passive"))
    )
    (net (code "126") (name "/N2_7") (class "Default")
      (node (ref "N2") (pin "K7") (pinfunction "7_K7") (pintype "bidirectional"))
      (node (ref "T27") (pin "3") (pinfunction "C_3") (pintype "passive"))
    )
    (net (code "127") (name "/N2_8") (class "Default")
      (node (ref "N2") (pin "K8") (pinfunction "8_K8") (pintype "bidirectional"))
      (node (ref "T28") (pin "3") (pinfunction "C_3") (pintype "passive"))
    )
    (net (code "128") (name "/N2_9") (class "Default")
      (node (ref "N2") (pin "K9") (pinfunction "9_K9") (pintype "bidirectional"))
      (node (ref "T29") (pin "3") (pinfunction "C_3") (pintype "passive"))
    )
    (net (code "129") (name "/N3_0") (class "Default")
      (node (ref "N3") (pin "K0") (pinfunction "0_K0") (pintype "bidirectional"))
      (node (ref "T30") (pin "3") (pinfunction "C_3") (pintype "passive"))
    )
    (net (code "130") (name "/N3_1") (class "Default")
      (node (ref "N3") (pin "K1") (pinfunction "1_K1") (pintype "bidirectional"))
      (node (ref "T31") (pin "3") (pinfunction "C_3") (pintype "passive"))
    )
    (net (code "131") (name "/N3_2") (class "Default")
      (node (ref "N3") (pin "K2") (pinfunction "2_K2") (pintype "bidirectional"))
      (node (ref "T32") (pin "3") (pinfunction "C_3") (pintype "passive"))
    )
    (net (code "132") (name "/N3_3") (class "Default")
      (node (ref "N3") (pin "K3") (pinfunction "3_K3") (pintype "bidirectional"))
      (node (ref "T33") (pin "3") (pinfunction "C_3") (pintype "passive"))
    )
    (net (code "133") (name "/N3_4") (class "Default")
      (node (ref "N3") (pin "K4") (pinfunction "4_K4") (pintype "bidirectional"))
      (node (ref "T34") (pin "3") (pinfunction "C_3") (pintype "passive"))
    )
    (net (code "134") (name "/N3_5") (class "Default")
      (node (ref "N3") (pin "K5") (pinfunction "5_K5") (pintype "bidirectional"))
      (node (ref "T35") (pin "3") (pinfunction "C_3") (pintype "passive"))
    )
    (net (code "135") (name "/N3_6") (class "Default")
      (node (ref "N3") (pin "K6") (pinfunction "6_K6") (pintype "bidirectional"))
      (node (ref "T36") (pin "3") (pinfunction "C_3") (pintype "passive"))
    )
    (net (code "136") (name "/N3_7") (class "Default")
      (node (ref "N3") (pin "K7") (pinfunction "7_K7") (pintype "bidirectional"))
      (node (ref "T37") (pin "3") (pinfunction "C_3") (pintype "passive"))
    )
    (net (code "137") (name "/N3_8") (class "Default")
      (node (ref "N3") (pin "K8") (pinfunction "8_K8") (pintype "bidirectional"))
      (node (ref "T38") (pin "3") (pinfunction "C_3") (pintype "passive"))
    )
    (net (code "138") (name "/N3_9") (class "Default")
      (node (ref "N3") (pin "K9") (pinfunction "9_K9") (pintype "bidirectional"))
      (node (ref "T39") (pin "3") (pinfunction "C_3") (pintype "passive"))
    )
    (net (code "139") (name "/RCK") (class "Default")
      (node (ref "IC1") (pin "12") (pinfunction "RCK_12") (pintype "input"))
      (node (ref "IC2") (pin "12") (pinfunction "RCK_12") (pintype "input"))
      (node (ref "IC3") (pin "12") (pinfunction "RCK_12") (pintype "input"))
      (node (ref "IC4") (pin "12") (pinfunction "RCK_12") (pintype "input"))
      (node (ref "IC5") (pin "12") (pinfunction "RCK_12") (pintype "input"))
      (node (ref "IC6") (pin "12") (pinfunction "RCK_12") (pintype "input"))
      (node (ref "JP1") (pin "9") (pinfunction "9_9") (pintype "passive"))
    )
    (net (code "140") (name "/SCK") (class "Default")
      (node (ref "IC1") (pin "11") (pinfunction "SCK_11") (pintype "input"))
      (node (ref "IC2") (pin "11") (pinfunction "SCK_11") (pintype "input"))
      (node (ref "IC3") (pin "11") (pinfunction "SCK_11") (pintype "input"))
      (node (ref "IC4") (pin "11") (pinfunction "SCK_11") (pintype "input"))
      (node (ref "IC5") (pin "11") (pinfunction "SCK_11") (pintype "input"))
      (node (ref "IC6") (pin "11") (pinfunction "SCK_11") (pintype "input"))
      (node (ref "JP1") (pin "10") (pinfunction "10_10") (pintype "passive"))
    )
    (net (code "141") (name "GND") (class "Default")
      (node (ref "C1") (pin "2") (pinfunction "2_2") (pintype "passive"))
      (node (ref "C2") (pin "2") (pinfunction "2_2") (pintype "passive"))
      (node (ref "C3") (pin "2") (pinfunction "2_2") (pintype "passive"))
      (node (ref "C4") (pin "2") (pinfunction "2_2") (pintype "passive"))
      (node (ref "C5") (pin "2") (pinfunction "2_2") (pintype "passive"))
      (node (ref "C6") (pin "2") (pinfunction "2_2") (pintype "passive"))
      (node (ref "IC1") (pin "8") (pinfunction "GND_8") (pintype "power_in"))
      (node (ref "IC2") (pin "8") (pinfunction "GND_8") (pintype "power_in"))
      (node (ref "IC3") (pin "8") (pinfunction "GND_8") (pintype "power_in"))
      (node (ref "IC4") (pin "8") (pinfunction "GND_8") (pintype "power_in"))
      (node (ref "IC5") (pin "8") (pinfunction "GND_8") (pintype "power_in"))
      (node (ref "IC6") (pin "8") (pinfunction "GND_8") (pintype "power_in"))
      (node (ref "JP1") (pin "2") (pinfunction "2_2") (pintype "passive"))
      (node (ref "JP1") (pin "3") (pinfunction "3_3") (pintype "passive"))
      (node (ref "JP1") (pin "4") (pinfunction "4_4") (pintype "passive"))
      (node (ref "JP1") (pin "5") (pinfunction "5_5") (pintype "passive"))
      (node (ref "R11") (pin "1") (pinfunction "1_1") (pintype "passive"))
      (node (ref "R21") (pin "1") (pinfunction "1_1") (pintype "passive"))
      (node (ref "R31") (pin "1") (pinfunction "1_1") (pintype "passive"))
      (node (ref "R41") (pin "1") (pinfunction "1_1") (pintype "passive"))
      (node (ref "T1") (pin "2") (pinfunction "E_2") (pintype "passive"))
      (node (ref "T10") (pin "2") (pinfunction "E_2") (pintype "passive"))
      (node (ref "T11") (pin "2") (pinfunction "E_2") (pintype "passive"))
      (node (ref "T12") (pin "2") (pinfunction "E_2") (pintype "passive"))
      (node (ref "T13") (pin "2") (pinfunction "E_2") (pintype "passive"))
      (node (ref "T14") (pin "2") (pinfunction "E_2") (pintype "passive"))
      (node (ref "T15") (pin "2") (pinfunction "E_2") (pintype "passive"))
      (node (ref "T16") (pin "2") (pinfunction "E_2") (pintype "passive"))
      (node (ref "T17") (pin "2") (pinfunction "E_2") (pintype "passive"))
      (node (ref "T18") (pin "2") (pinfunction "E_2") (pintype "passive"))
      (node (ref "T19") (pin "2") (pinfunction "E_2") (pintype "passive"))
      (node (ref "T2") (pin "2") (pinfunction "E_2") (pintype "passive"))
      (node (ref "T20") (pin "2") (pinfunction "E_2") (pintype "passive"))
      (node (ref "T21") (pin "2") (pinfunction "E_2") (pintype "passive"))
      (node (ref "T22") (pin "2") (pinfunction "E_2") (pintype "passive"))
      (node (ref "T23") (pin "2") (pinfunction "E_2") (pintype "passive"))
      (node (ref "T24") (pin "2") (pinfunction "E_2") (pintype "passive"))
      (node (ref "T25") (pin "2") (pinfunction "E_2") (pintype "passive"))
      (node (ref "T26") (pin "2") (pinfunction "E_2") (pintype "passive"))
      (node (ref "T27") (pin "2") (pinfunction "E_2") (pintype "passive"))
      (node (ref "T28") (pin "2") (pinfunction "E_2") (pintype "passive"))
      (node (ref "T29") (pin "2") (pinfunction "E_2") (pintype "passive"))
      (node (ref "T30") (pin "2") (pinfunction "E_2") (pintype "passive"))
      (node (ref "T31") (pin "2") (pinfunction "E_2") (pintype "passive"))
      (node (ref "T32") (pin "2") (pinfunction "E_2") (pintype "passive"))
      (node (ref "T33") (pin "2") (pinfunction "E_2") (pintype "passive"))
      (node (ref "T34") (pin "2") (pinfunction "E_2") (pintype "passive"))
      (node (ref "T35") (pin "2") (pinfunction "E_2") (pintype "passive"))
      (node (ref "T36") (pin "2") (pinfunction "E_2") (pintype "passive"))
      (node (ref "T37") (pin "2") (pinfunction "E_2") (pintype "passive"))
      (node (ref "T38") (pin "2") (pinfunction "E_2") (pintype "passive"))
      (node (ref "T39") (pin "2") (pinfunction "E_2") (pintype "passive"))
      (node (ref "T40") (pin "2") (pinfunction "E_2") (pintype "passive"))
      (node (ref "T41") (pin "2") (pinfunction "E_2") (pintype "passive"))
      (node (ref "T42") (pin "2") (pinfunction "E_2") (pintype "passive"))
      (node (ref "T43") (pin "2") (pinfunction "E_2") (pintype "passive"))
      (node (ref "T44") (pin "2") (pinfunction "E_2") (pintype "passive"))
      (node (ref "T45") (pin "2") (pinfunction "E_2") (pintype "passive"))
      (node (ref "T46") (pin "2") (pinfunction "E_2") (pintype "passive"))
      (node (ref "T47") (pin "2") (pinfunction "E_2") (pintype "passive"))
      (node (ref "T48") (pin "2") (pinfunction "E_2") (pintype "passive"))
      (node (ref "T49") (pin "2") (pinfunction "E_2") (pintype "passive"))
    )
    (net (code "142") (name "Net-(GL1-A)") (class "Default")
      (node (ref "GL1") (pin "1") (pinfunction "A_1") (pintype "passive"))
      (node (ref "R1") (pin "1") (pinfunction "1_1") (pintype "passive"))
    )
    (net (code "143") (name "Net-(GL1-A1)") (class "Default")
      (node (ref "GL1") (pin "2") (pinfunction "A1_2") (pintype "passive"))
      (node (ref "T1") (pin "3") (pinfunction "C_3") (pintype "passive"))
    )
    (net (code "144") (name "Net-(GL2-A)") (class "Default")
      (node (ref "GL2") (pin "1") (pinfunction "A_1") (pintype "passive"))
      (node (ref "R2") (pin "1") (pinfunction "1_1") (pintype "passive"))
    )
    (net (code "145") (name "Net-(GL2-A1)") (class "Default")
      (node (ref "GL2") (pin "2") (pinfunction "A1_2") (pintype "passive"))
      (node (ref "T2") (pin "3") (pinfunction "C_3") (pintype "passive"))
    )
    (net (code "146") (name "Net-(IC1A-QH*)") (class "Default")
      (node (ref "IC1") (pin "9") (pinfunction "QH*_9") (pintype "tri_state"))
      (node (ref "IC2") (pin "14") (pinfunction "SER_14") (pintype "input"))
    )
    (net (code "147") (name "Net-(IC2A-QH*)") (class "Default")
      (node (ref "IC2") (pin "9") (pinfunction "QH*_9") (pintype "tri_state"))
      (node (ref "IC3") (pin "14") (pinfunction "SER_14") (pintype "input"))
    )
    (net (code "148") (name "Net-(IC3A-QH*)") (class "Default")
      (node (ref "IC3") (pin "9") (pinfunction "QH*_9") (pintype "tri_state"))
      (node (ref "IC4") (pin "14") (pinfunction "SER_14") (pintype "input"))
    )
    (net (code "149") (name "Net-(IC4A-QH*)") (class "Default")
      (node (ref "IC4") (pin "9") (pinfunction "QH*_9") (pintype "tri_state"))
      (node (ref "IC5") (pin "14") (pinfunction "SER_14") (pintype "input"))
    )
    (net (code "150") (name "Net-(IC5A-QH*)") (class "Default")
      (node (ref "IC5") (pin "9") (pinfunction "QH*_9") (pintype "tri_state"))
      (node (ref "IC6") (pin "14") (pinfunction "SER_14") (pintype "input"))
    )
    (net (code "151") (name "Net-(N1-A-PadA1)") (class "Default")
      (node (ref "N1") (pin "A1") (pinfunction "A_A1") (pintype "bidirectional"))
      (node (ref "N1") (pin "A2") (pinfunction "A_A2") (pintype "bidirectional"))
      (node (ref "R10") (pin "1") (pinfunction "1_1") (pintype "passive"))
    )
    (net (code "152") (name "Net-(N1-PadPR)") (class "Default")
      (node (ref "N1") (pin "PR") (pinfunction "PR_PR") (pintype "bidirectional"))
      (node (ref "R11") (pin "2") (pinfunction "2_2") (pintype "passive"))
    )
    (net (code "153") (name "Net-(N2-A-PadA1)") (class "Default")
      (node (ref "N2") (pin "A1") (pinfunction "A_A1") (pintype "bidirectional"))
      (node (ref "N2") (pin "A2") (pinfunction "A_A2") (pintype "bidirectional"))
      (node (ref "R20") (pin "1") (pinfunction "1_1") (pintype "passive"))
    )
    (net (code "154") (name "Net-(N2-PadPR)") (class "Default")
      (node (ref "N2") (pin "PR") (pinfunction "PR_PR") (pintype "bidirectional"))
      (node (ref "R21") (pin "2") (pinfunction "2_2") (pintype "passive"))
    )
    (net (code "155") (name "Net-(N3-A-PadA1)") (class "Default")
      (node (ref "N3") (pin "A1") (pinfunction "A_A1") (pintype "bidirectional"))
      (node (ref "N3") (pin "A2") (pinfunction "A_A2") (pintype "bidirectional"))
      (node (ref "R30") (pin "1") (pinfunction "1_1") (pintype "passive"))
    )
    (net (code "156") (name "Net-(N3-PadPR)") (class "Default")
      (node (ref "N3") (pin "PR") (pinfunction "PR_PR") (pintype "bidirectional"))
      (node (ref "R31") (pin "2") (pinfunction "2_2") (pintype "passive"))
    )
    (net (code "157") (name "Net-(N4-A-PadA1)") (class "Default")
      (node (ref "N4") (pin "A1") (pinfunction "A_A1") (pintype "bidirectional"))
      (node (ref "N4") (pin "A2") (pinfunction "A_A2") (pintype "bidirectional"))
      (node (ref "R40") (pin "1") (pinfunction "1_1") (pintype "passive"))
    )
    (net (code "158") (name "Net-(N4-PadPR)") (class "Default")
      (node (ref "N4") (pin "PR") (pinfunction "PR_PR") (pintype "bidirectional"))
      (node (ref "R41") (pin "2") (pinfunction "2_2") (pintype "passive"))
    )
    (net (code "159") (name "VDD") (class "Default")
      (node (ref "JP1") (pin "1") (pinfunction "1_1") (pintype "passive"))
      (node (ref "R1") (pin "2") (pinfunction "2_2") (pintype "passive"))
      (node (ref "R10") (pin "2") (pinfunction "2_2") (pintype "passive"))
      (node (ref "R2") (pin "2") (pinfunction "2_2") (pintype "passive"))
      (node (ref "R20") (pin "2") (pinfunction "2_2") (pintype "passive"))
      (node (ref "R30") (pin "2") (pinfunction "2_2") (pintype "passive"))
      (node (ref "R40") (pin "2") (pinfunction "2_2") (pintype "passive"))
    )
    (net (code "160") (name "unconnected-(IC1A-SCL-Pad10)") (class "Default")
      (node (ref "IC1") (pin "10") (pinfunction "SCL_10") (pintype "input"))
    )
    (net (code "161") (name "unconnected-(IC2A-SCL-Pad10)") (class "Default")
      (node (ref "IC2") (pin "10") (pinfunction "SCL_10") (pintype "input"))
    )
    (net (code "162") (name "unconnected-(IC3A-SCL-Pad10)") (class "Default")
      (node (ref "IC3") (pin "10") (pinfunction "SCL_10") (pintype "input"))
    )
    (net (code "163") (name "unconnected-(IC4A-SCL-Pad10)") (class "Default")
      (node (ref "IC4") (pin "10") (pinfunction "SCL_10") (pintype "input"))
    )
    (net (code "164") (name "unconnected-(IC5A-SCL-Pad10)") (class "Default")
      (node (ref "IC5") (pin "10") (pinfunction "SCL_10") (pintype "input"))
    )
    (net (code "165") (name "unconnected-(IC6A-QH*-Pad9)") (class "Default")
      (node (ref "IC6") (pin "9") (pinfunction "QH*_9") (pintype "tri_state"))
    )
    (net (code "166") (name "unconnected-(IC6A-SCL-Pad10)") (class "Default")
      (node (ref "IC6") (pin "10") (pinfunction "SCL_10") (pintype "input"))
    )
    (net (code "167") (name "unconnected-(N2-DP-PadKDP)") (class "Default")
      (node (ref "N2") (pin "KDP") (pinfunction "DP_KDP") (pintype "bidirectional"))
    )
    (net (code "168") (name "unconnected-(N3-DP-PadKDP)") (class "Default")
      (node (ref "N3") (pin "KDP") (pinfunction "DP_KDP") (pintype "bidirectional"))
    )
    (net (code "169") (name "unconnected-(N4-DP-PadKDP)") (class "Default")
      (node (ref "N4") (pin "KDP") (pinfunction "DP_KDP") (pintype "bidirectional"))
    )
    (net (code "170") (name "unconnected-(RN31-Pad7)") (class "Default")
      (node (ref "RN31") (pin "7") (pinfunction "7_7") (pintype "passive"))
    )
    (net (code "171") (name "unconnected-(RN31-Pad8)") (class "Default")
      (node (ref "RN31") (pin "8") (pinfunction "8_8") (pintype "passive"))
    )
  )
)
